# template.net
KiCad netlist of a schematic drawn in Altium Designer
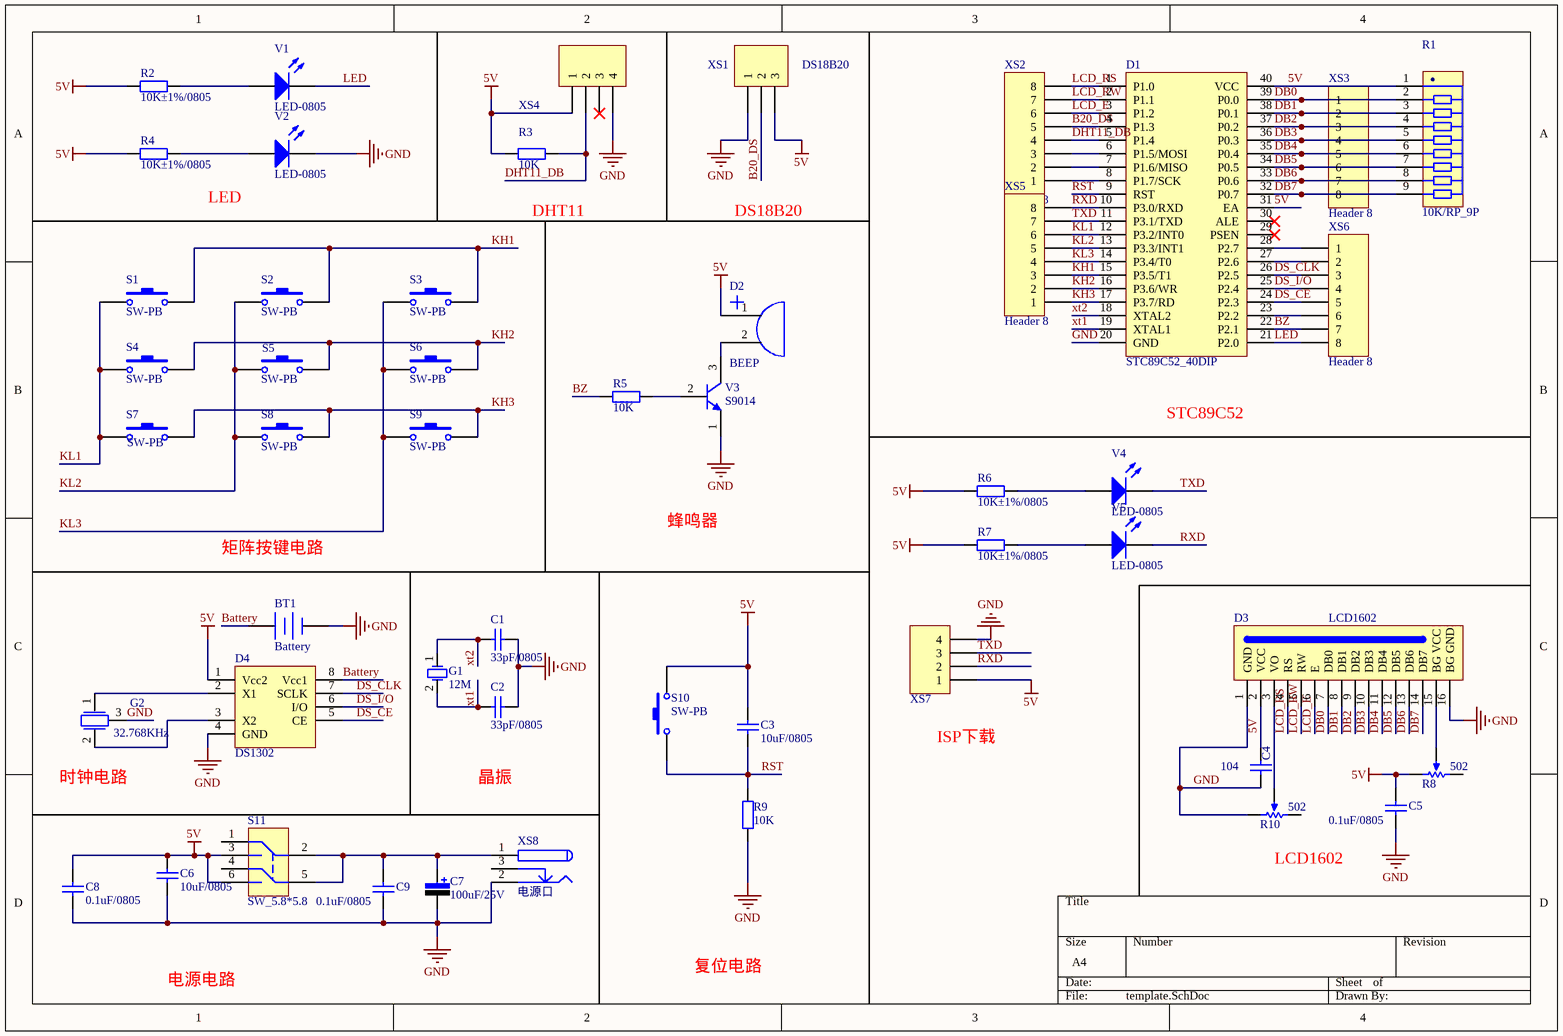
[diagram p0: template.SchDoc]

(export (version "E")
  (design (tool "Eeschema 10.0.6"))
  (components
    (comp (ref "BT1")
      (value "Battery")
      (footprint "CR1220")
      (description "备份电池")
      (fields (field (name "PUBLISHER") "Altium Limited"))
      (libsource (lib "connector") (part "Battery"))
    )
    (comp (ref "C1")
      (value "33pF/0805")
      (footprint "C 0805")
      (description "无极性贴片电容")
      (fields (field (name "PUBLISHER") "Altium Limited"))
      (libsource (lib "C_L_R") (part "Cap1"))
    )
    (comp (ref "C2")
      (value "33pF/0805")
      (footprint "C 0805")
      (description "无极性贴片电容")
      (fields (field (name "PUBLISHER") "Altium Limited"))
      (libsource (lib "C_L_R") (part "Cap1"))
    )
    (comp (ref "C3")
      (value "10uF/0805")
      (footprint "C 0805")
      (description "无极性贴片电容")
      (fields (field (name "PUBLISHER") "Altium Limited"))
      (libsource (lib "C_L_R") (part "Cap1"))
    )
    (comp (ref "C4")
      (value "104")
      (footprint "C 0805")
      (description "无极性贴片电容")
      (fields (field (name "PUBLISHER") "Altium Limited"))
      (libsource (lib "C_L_R") (part "Cap1"))
    )
    (comp (ref "C5")
      (value "0.1uF/0805")
      (footprint "C 0805")
      (description "无极性贴片电容")
      (fields (field (name "PUBLISHER") "Altium Limited"))
      (libsource (lib "C_L_R") (part "Cap1"))
    )
    (comp (ref "C6")
      (value "10uF/0805")
      (footprint "C 0805")
      (description "无极性贴片电容")
      (fields (field (name "PUBLISHER") "Altium Limited"))
      (libsource (lib "C_L_R") (part "Cap1"))
    )
    (comp (ref "C7")
      (value "100uF/25V")
      (footprint "C-RB-D6.3")
      (description "贴片极性电解电容")
      (fields (field (name "PUBLISHER") "Altium Limited"))
      (libsource (lib "C_L_R") (part "Cap Pol2"))
    )
    (comp (ref "C8")
      (value "0.1uF/0805")
      (footprint "C 0805")
      (description "无极性贴片电容")
      (fields (field (name "PUBLISHER") "Altium Limited"))
      (libsource (lib "C_L_R") (part "Cap1"))
    )
    (comp (ref "C9")
      (value "0.1uF/0805")
      (footprint "C 0805")
      (description "无极性贴片电容")
      (fields (field (name "PUBLISHER") "Altium Limited"))
      (libsource (lib "C_L_R") (part "Cap1"))
    )
    (comp (ref "D1")
      (value "STC89C52_40DIP")
      (footprint "STC89C52底座")
      (description "40 DIP")
      (libsource (lib "chip") (part "STC89C52_40DIP"))
    )
    (comp (ref "D2")
      (value "BEEP")
      (footprint "Beep")
      (description "蜂鸣器")
      (libsource (lib "chip") (part "BEEP"))
    )
    (comp (ref "D3")
      (value "LCD1602")
      (footprint "LCD1602接口")
      (description "LCD1602接口，16P")
      (libsource (lib "chip") (part "LCD1602接口"))
    )
    (comp (ref "D4")
      (value "DS1302")
      (footprint "DS1302")
      (description "实时时钟芯片")
      (libsource (lib "chip") (part "DS1302"))
    )
    (comp (ref "G1")
      (value "12M")
      (footprint "XTAL-HC-49S")
      (description "2脚晶振")
      (fields (field (name "PUBLISHER") "Altium Limited"))
      (libsource (lib "chip") (part "XTAL-2P"))
    )
    (comp (ref "G2")
      (value "32.768KHz")
      (footprint "XTAL-TC15")
      (description "3脚晶振")
      (libsource (lib "chip") (part "XTAL-3P"))
    )
    (comp (ref "R1")
      (value "10K/RP_9P")
      (footprint "RP_9P")
      (description "9P排阻")
      (libsource (lib "C_L_R") (part "RP_9P"))
    )
    (comp (ref "R2")
      (value "10K±1%/0805")
      (footprint "R 0805")
      (description "贴片电阻")
      (fields (field (name "PUBLISHER") "Altium Limited"))
      (libsource (lib "C_L_R") (part "Res1"))
    )
    (comp (ref "R3")
      (value "10K")
      (footprint "R 0805")
      (description "贴片电阻")
      (fields (field (name "PUBLISHER") "Altium Limited"))
      (libsource (lib "C_L_R") (part "Res1"))
    )
    (comp (ref "R4")
      (value "10K±1%/0805")
      (footprint "R 0805")
      (description "贴片电阻")
      (fields (field (name "PUBLISHER") "Altium Limited"))
      (libsource (lib "C_L_R") (part "Res1"))
    )
    (comp (ref "R5")
      (value "10K")
      (footprint "R 0805")
      (description "贴片电阻")
      (fields (field (name "PUBLISHER") "Altium Limited"))
      (libsource (lib "C_L_R") (part "Res1"))
    )
    (comp (ref "R6")
      (value "10K±1%/0805")
      (footprint "R 0805")
      (description "贴片电阻")
      (fields (field (name "PUBLISHER") "Altium Limited"))
      (libsource (lib "C_L_R") (part "Res1"))
    )
    (comp (ref "R7")
      (value "10K±1%/0805")
      (footprint "R 0805")
      (description "贴片电阻")
      (fields (field (name "PUBLISHER") "Altium Limited"))
      (libsource (lib "C_L_R") (part "Res1"))
    )
    (comp (ref "R8")
      (value "502")
      (footprint "RP")
      (description "精密可调电阻")
      (fields (field (name "PUBLISHER") "Altium Limited"))
      (libsource (lib "C_L_R") (part "RPot"))
    )
    (comp (ref "R9")
      (value "10K")
      (footprint "R 0805")
      (description "贴片电阻")
      (fields (field (name "PUBLISHER") "Altium Limited"))
      (libsource (lib "") (part "Res1_1"))
    )
    (comp (ref "R10")
      (value "502")
      (footprint "RP")
      (description "精密可调电阻")
      (fields (field (name "PUBLISHER") "Altium Limited"))
      (libsource (lib "C_L_R") (part "RPot"))
    )
    (comp (ref "S1")
      (value "SW-PB")
      (footprint "SW_PB2_A1")
      (description "微动开关")
      (fields (field (name "PUBLISHER") "Altium Limited"))
      (libsource (lib "connector") (part "SW-PB"))
    )
    (comp (ref "S2")
      (value "SW-PB")
      (footprint "SW_PB2_A1")
      (description "微动开关")
      (fields (field (name "PUBLISHER") "Altium Limited"))
      (libsource (lib "connector") (part "SW-PB"))
    )
    (comp (ref "S3")
      (value "SW-PB")
      (footprint "SW_PB2_A1")
      (description "微动开关")
      (fields (field (name "PUBLISHER") "Altium Limited"))
      (libsource (lib "connector") (part "SW-PB"))
    )
    (comp (ref "S4")
      (value "SW-PB")
      (footprint "SW_PB2_A1")
      (description "微动开关")
      (fields (field (name "PUBLISHER") "Altium Limited"))
      (libsource (lib "connector") (part "SW-PB"))
    )
    (comp (ref "S5")
      (value "SW-PB")
      (footprint "SW_PB2_A1")
      (description "微动开关")
      (fields (field (name "PUBLISHER") "Altium Limited"))
      (libsource (lib "connector") (part "SW-PB"))
    )
    (comp (ref "S6")
      (value "SW-PB")
      (footprint "SW_PB2_A1")
      (description "微动开关")
      (fields (field (name "PUBLISHER") "Altium Limited"))
      (libsource (lib "connector") (part "SW-PB"))
    )
    (comp (ref "S7")
      (value "SW-PB")
      (footprint "SW_PB2_A1")
      (description "微动开关")
      (fields (field (name "PUBLISHER") "Altium Limited"))
      (libsource (lib "connector") (part "SW-PB"))
    )
    (comp (ref "S8")
      (value "SW-PB")
      (footprint "SW_PB2_A1")
      (description "微动开关")
      (fields (field (name "PUBLISHER") "Altium Limited"))
      (libsource (lib "connector") (part "SW-PB"))
    )
    (comp (ref "S9")
      (value "SW-PB")
      (footprint "SW_PB2_A1")
      (description "微动开关")
      (fields (field (name "PUBLISHER") "Altium Limited"))
      (libsource (lib "connector") (part "SW-PB"))
    )
    (comp (ref "S10")
      (value "SW-PB")
      (footprint "SW_PB2_A1")
      (description "微动开关")
      (fields (field (name "PUBLISHER") "Altium Limited"))
      (libsource (lib "connector") (part "SW-PB"))
    )
    (comp (ref "S11")
      (value "SW_5.8*5.8")
      (footprint "SW-5.8")
      (description "6脚自锁开关")
      (libsource (lib "connector") (part "SW-6脚自锁开关"))
    )
    (comp (ref "V1")
      (value "LED-0805")
      (footprint "LED-0805")
      (description "发光二极管")
      (fields (field (name "PUBLISHER") "Altium Limited"))
      (libsource (lib "C_L_R") (part "LED0"))
    )
    (comp (ref "V2")
      (value "LED-0805")
      (footprint "LED-0805")
      (description "发光二极管")
      (fields (field (name "PUBLISHER") "Altium Limited"))
      (libsource (lib "C_L_R") (part "LED0"))
    )
    (comp (ref "V3")
      (value "S9014")
      (footprint "SS9014")
      (description "NPN三极管")
      (fields (field (name "PUBLISHER") "Altium Limited"))
      (libsource (lib "chip") (part "S9014"))
    )
    (comp (ref "V4")
      (value "LED-0805")
      (footprint "LED-0805")
      (description "发光二极管")
      (fields (field (name "PUBLISHER") "Altium Limited"))
      (libsource (lib "C_L_R") (part "LED0"))
    )
    (comp (ref "V5")
      (value "LED-0805")
      (footprint "LED-0805")
      (description "发光二极管")
      (fields (field (name "PUBLISHER") "Altium Limited"))
      (libsource (lib "C_L_R") (part "LED0"))
    )
    (comp (ref "XS1")
      (value "DS18B20")
      (footprint "HDR3X1_A")
      (description "接插件")
      (fields (field (name "PUBLISHER") "Altium Limited"))
      (libsource (lib "connector") (part "Header 3"))
    )
    (comp (ref "XS2")
      (value "Header 8")
      (footprint "HDR8X1_A")
      (description "Header, 8-Pin")
      (fields (field (name "PUBLISHER") "Altium Limited"))
      (libsource (lib "connector") (part "Header 8"))
    )
    (comp (ref "XS3")
      (value "Header 8")
      (footprint "HDR8X1_A")
      (description "Header, 8-Pin")
      (fields (field (name "PUBLISHER") "Altium Limited"))
      (libsource (lib "") (part "Header 8_1"))
    )
    (comp (ref "XS4")
      (value "Header 4")
      (footprint "HDR4X1_A")
      (description "接插件")
      (fields (field (name "PUBLISHER") "Altium Limited"))
      (libsource (lib "") (part "Header 4_1"))
    )
    (comp (ref "XS5")
      (value "Header 8")
      (footprint "HDR8X1_A")
      (description "Header, 8-Pin")
      (fields (field (name "PUBLISHER") "Altium Limited"))
      (libsource (lib "connector") (part "Header 8"))
    )
    (comp (ref "XS6")
      (value "Header 8")
      (footprint "HDR8X1_A")
      (description "Header, 8-Pin")
      (fields (field (name "PUBLISHER") "Altium Limited"))
      (libsource (lib "") (part "Header 8_1"))
    )
    (comp (ref "XS7")
      (value "Header 4")
      (footprint "HDR4X1_A")
      (description "接插件")
      (fields (field (name "PUBLISHER") "Altium Limited"))
      (libsource (lib "connector") (part "Header 4"))
    )
    (comp (ref "XS8")
      (value "电源口")
      (footprint "DC-005")
      (description "直流电源端子")
      (fields (field (name "PUBLISHER") "Altium Limited"))
      (libsource (lib "connector") (part "DC connector"))
    )
  )
  (nets
    (net (code "1") (name "/B20_DS") (class "Default")
      (node (ref "D1") (pin "4") (pinfunction "P1.3_4") (pintype "passive"))
      (node (ref "XS1") (pin "2") (pinfunction "2_2") (pintype "passive"))
      (node (ref "XS2") (pin "5") (pinfunction "5_5") (pintype "passive"))
    )
    (net (code "2") (name "/BZ") (class "Default")
      (node (ref "D1") (pin "22") (pinfunction "P2.1_22") (pintype "passive"))
      (node (ref "R5") (pin "1") (pinfunction "1_1") (pintype "passive"))
      (node (ref "XS6") (pin "7") (pinfunction "7_7") (pintype "passive"))
    )
    (net (code "3") (name "/Battery") (class "Default")
      (node (ref "BT1") (pin "1") (pinfunction "+_1") (pintype "passive"))
      (node (ref "D4") (pin "8") (pinfunction "Vcc1_8") (pintype "passive"))
    )
    (net (code "4") (name "/DB0") (class "Default")
      (node (ref "D1") (pin "39") (pinfunction "P0.0_39") (pintype "passive"))
      (node (ref "D3") (pin "7") (pinfunction "DB0_7") (pintype "passive"))
      (node (ref "R1") (pin "2") (pinfunction "2_2") (pintype "power_in"))
      (node (ref "XS3") (pin "1") (pinfunction "1_1") (pintype "passive"))
    )
    (net (code "5") (name "/DB1") (class "Default")
      (node (ref "D1") (pin "38") (pinfunction "P0.1_38") (pintype "passive"))
      (node (ref "D3") (pin "8") (pinfunction "DB1_8") (pintype "passive"))
      (node (ref "R1") (pin "3") (pinfunction "3_3") (pintype "power_in"))
      (node (ref "XS3") (pin "2") (pinfunction "2_2") (pintype "passive"))
    )
    (net (code "6") (name "/DB2") (class "Default")
      (node (ref "D1") (pin "37") (pinfunction "P0.2_37") (pintype "passive"))
      (node (ref "D3") (pin "9") (pinfunction "DB2_9") (pintype "passive"))
      (node (ref "R1") (pin "4") (pinfunction "4_4") (pintype "power_in"))
      (node (ref "XS3") (pin "3") (pinfunction "3_3") (pintype "passive"))
    )
    (net (code "7") (name "/DB3") (class "Default")
      (node (ref "D1") (pin "36") (pinfunction "P0.3_36") (pintype "passive"))
      (node (ref "D3") (pin "10") (pinfunction "DB3_10") (pintype "passive"))
      (node (ref "R1") (pin "5") (pinfunction "5_5") (pintype "power_in"))
      (node (ref "XS3") (pin "4") (pinfunction "4_4") (pintype "passive"))
    )
    (net (code "8") (name "/DB4") (class "Default")
      (node (ref "D1") (pin "35") (pinfunction "P0.4_35") (pintype "passive"))
      (node (ref "D3") (pin "11") (pinfunction "DB4_11") (pintype "passive"))
      (node (ref "R1") (pin "6") (pinfunction "6_6") (pintype "power_in"))
      (node (ref "XS3") (pin "5") (pinfunction "5_5") (pintype "passive"))
    )
    (net (code "9") (name "/DB5") (class "Default")
      (node (ref "D1") (pin "34") (pinfunction "P0.5_34") (pintype "passive"))
      (node (ref "D3") (pin "12") (pinfunction "DB5_12") (pintype "passive"))
      (node (ref "R1") (pin "7") (pinfunction "7_7") (pintype "power_in"))
      (node (ref "XS3") (pin "6") (pinfunction "6_6") (pintype "passive"))
    )
    (net (code "10") (name "/DB6") (class "Default")
      (node (ref "D1") (pin "33") (pinfunction "P0.6_33") (pintype "passive"))
      (node (ref "D3") (pin "13") (pinfunction "DB6_13") (pintype "passive"))
      (node (ref "R1") (pin "8") (pinfunction "8_8") (pintype "power_in"))
      (node (ref "XS3") (pin "7") (pinfunction "7_7") (pintype "passive"))
    )
    (net (code "11") (name "/DB7") (class "Default")
      (node (ref "D1") (pin "32") (pinfunction "P0.7_32") (pintype "passive"))
      (node (ref "D3") (pin "14") (pinfunction "DB7_14") (pintype "passive"))
      (node (ref "R1") (pin "9") (pinfunction "9_9") (pintype "power_in"))
      (node (ref "XS3") (pin "8") (pinfunction "8_8") (pintype "passive"))
    )
    (net (code "12") (name "/DHT11_DB") (class "Default")
      (node (ref "D1") (pin "5") (pinfunction "P1.4_5") (pintype "passive"))
      (node (ref "R3") (pin "2") (pinfunction "2_2") (pintype "passive"))
      (node (ref "XS2") (pin "4") (pinfunction "4_4") (pintype "passive"))
      (node (ref "XS4") (pin "2") (pinfunction "2_2") (pintype "passive"))
    )
    (net (code "13") (name "/DS_CE") (class "Default")
      (node (ref "D1") (pin "24") (pinfunction "P2.3_24") (pintype "passive"))
      (node (ref "D4") (pin "5") (pinfunction "CE_5") (pintype "passive"))
      (node (ref "XS6") (pin "5") (pinfunction "5_5") (pintype "passive"))
    )
    (net (code "14") (name "/DS_CLK") (class "Default")
      (node (ref "D1") (pin "26") (pinfunction "P2.5_26") (pintype "passive"))
      (node (ref "D4") (pin "7") (pinfunction "SCLK_7") (pintype "passive"))
      (node (ref "XS6") (pin "3") (pinfunction "3_3") (pintype "passive"))
    )
    (net (code "15") (name "/DS_I{slash}O") (class "Default")
      (node (ref "D1") (pin "25") (pinfunction "P2.4_25") (pintype "passive"))
      (node (ref "D4") (pin "6") (pinfunction "I/O_6") (pintype "passive"))
      (node (ref "XS6") (pin "4") (pinfunction "4_4") (pintype "passive"))
    )
    (net (code "16") (name "/KH1") (class "Default")
      (node (ref "D1") (pin "15") (pinfunction "P3.5/T1_15") (pintype "passive"))
      (node (ref "S1") (pin "2") (pinfunction "2_2") (pintype "passive"))
      (node (ref "S2") (pin "2") (pinfunction "2_2") (pintype "passive"))
      (node (ref "S3") (pin "2") (pinfunction "2_2") (pintype "passive"))
      (node (ref "XS5") (pin "3") (pinfunction "3_3") (pintype "passive"))
    )
    (net (code "17") (name "/KH2") (class "Default")
      (node (ref "D1") (pin "16") (pinfunction "P3.6/WR_16") (pintype "passive"))
      (node (ref "S4") (pin "2") (pinfunction "2_2") (pintype "passive"))
      (node (ref "S5") (pin "2") (pinfunction "2_2") (pintype "passive"))
      (node (ref "S6") (pin "2") (pinfunction "2_2") (pintype "passive"))
      (node (ref "XS5") (pin "2") (pinfunction "2_2") (pintype "passive"))
    )
    (net (code "18") (name "/KH3") (class "Default")
      (node (ref "D1") (pin "17") (pinfunction "P3.7/RD_17") (pintype "passive"))
      (node (ref "S7") (pin "2") (pinfunction "2_2") (pintype "passive"))
      (node (ref "S8") (pin "2") (pinfunction "2_2") (pintype "passive"))
      (node (ref "S9") (pin "2") (pinfunction "2_2") (pintype "passive"))
      (node (ref "XS5") (pin "1") (pinfunction "1_1") (pintype "passive"))
    )
    (net (code "19") (name "/KL1") (class "Default")
      (node (ref "D1") (pin "12") (pinfunction "P3.2/INT0_12") (pintype "passive"))
      (node (ref "S1") (pin "1") (pinfunction "1_1") (pintype "passive"))
      (node (ref "S4") (pin "1") (pinfunction "1_1") (pintype "passive"))
      (node (ref "S7") (pin "1") (pinfunction "1_1") (pintype "passive"))
      (node (ref "XS5") (pin "6") (pinfunction "6_6") (pintype "passive"))
    )
    (net (code "20") (name "/KL2") (class "Default")
      (node (ref "D1") (pin "13") (pinfunction "P3.3/INT1_13") (pintype "passive"))
      (node (ref "S2") (pin "1") (pinfunction "1_1") (pintype "passive"))
      (node (ref "S5") (pin "1") (pinfunction "1_1") (pintype "passive"))
      (node (ref "S8") (pin "1") (pinfunction "1_1") (pintype "passive"))
      (node (ref "XS5") (pin "5") (pinfunction "5_5") (pintype "passive"))
    )
    (net (code "21") (name "/KL3") (class "Default")
      (node (ref "D1") (pin "14") (pinfunction "P3.4/T0_14") (pintype "passive"))
      (node (ref "S3") (pin "1") (pinfunction "1_1") (pintype "passive"))
      (node (ref "S6") (pin "1") (pinfunction "1_1") (pintype "passive"))
      (node (ref "S9") (pin "1") (pinfunction "1_1") (pintype "passive"))
      (node (ref "XS5") (pin "4") (pinfunction "4_4") (pintype "passive"))
    )
    (net (code "22") (name "/LCD_E") (class "Default")
      (node (ref "D1") (pin "3") (pinfunction "P1.2_3") (pintype "passive"))
      (node (ref "D3") (pin "6") (pinfunction "E_6") (pintype "passive"))
      (node (ref "XS2") (pin "6") (pinfunction "6_6") (pintype "passive"))
    )
    (net (code "23") (name "/LCD_RS") (class "Default")
      (node (ref "D1") (pin "1") (pinfunction "P1.0_1") (pintype "passive"))
      (node (ref "D3") (pin "4") (pinfunction "RS_4") (pintype "passive"))
      (node (ref "XS2") (pin "8") (pinfunction "8_8") (pintype "passive"))
    )
    (net (code "24") (name "/LCD_RW") (class "Default")
      (node (ref "D1") (pin "2") (pinfunction "P1.1_2") (pintype "passive"))
      (node (ref "D3") (pin "5") (pinfunction "RW_5") (pintype "passive"))
      (node (ref "XS2") (pin "7") (pinfunction "7_7") (pintype "passive"))
    )
    (net (code "25") (name "/LED") (class "Default")
      (node (ref "D1") (pin "21") (pinfunction "P2.0_21") (pintype "passive"))
      (node (ref "V1") (pin "2") (pinfunction "K_2") (pintype "passive"))
      (node (ref "XS6") (pin "8") (pinfunction "8_8") (pintype "passive"))
    )
    (net (code "26") (name "/RST") (class "Default")
      (node (ref "C3") (pin "1") (pinfunction "1_1") (pintype "passive"))
      (node (ref "D1") (pin "9") (pinfunction "RST_9") (pintype "passive"))
      (node (ref "R9") (pin "2") (pinfunction "2_2") (pintype "passive"))
      (node (ref "S10") (pin "1") (pinfunction "1_1") (pintype "passive"))
    )
    (net (code "27") (name "/RXD") (class "Default")
      (node (ref "D1") (pin "10") (pinfunction "P3.0/RXD_10") (pintype "passive"))
      (node (ref "V5") (pin "2") (pinfunction "K_2") (pintype "passive"))
      (node (ref "XS5") (pin "8") (pinfunction "8_8") (pintype "passive"))
      (node (ref "XS7") (pin "2") (pinfunction "2_2") (pintype "passive"))
    )
    (net (code "28") (name "/TXD") (class "Default")
      (node (ref "D1") (pin "11") (pinfunction "P3.1/TXD_11") (pintype "passive"))
      (node (ref "V4") (pin "2") (pinfunction "K_2") (pintype "passive"))
      (node (ref "XS5") (pin "7") (pinfunction "7_7") (pintype "passive"))
      (node (ref "XS7") (pin "3") (pinfunction "3_3") (pintype "passive"))
    )
    (net (code "29") (name "/xt1") (class "Default")
      (node (ref "C2") (pin "2") (pinfunction "2_2") (pintype "passive"))
      (node (ref "D1") (pin "19") (pinfunction "XTAL1_19") (pintype "passive"))
      (node (ref "G1") (pin "2") (pinfunction "2_2") (pintype "passive"))
    )
    (net (code "30") (name "/xt2") (class "Default")
      (node (ref "C1") (pin "1") (pinfunction "1_1") (pintype "passive"))
      (node (ref "D1") (pin "18") (pinfunction "XTAL2_18") (pintype "passive"))
      (node (ref "G1") (pin "1") (pinfunction "1_1") (pintype "passive"))
    )
    (net (code "31") (name "5V") (class "Default")
      (node (ref "C3") (pin "2") (pinfunction "2_2") (pintype "passive"))
      (node (ref "C4") (pin "2") (pinfunction "2_2") (pintype "passive"))
      (node (ref "C5") (pin "2") (pinfunction "2_2") (pintype "passive"))
      (node (ref "C6") (pin "2") (pinfunction "2_2") (pintype "passive"))
      (node (ref "C8") (pin "2") (pinfunction "2_2") (pintype "passive"))
      (node (ref "D1") (pin "31") (pinfunction "EA_31") (pintype "passive"))
      (node (ref "D1") (pin "40") (pinfunction "VCC_40") (pintype "passive"))
      (node (ref "D2") (pin "1") (pinfunction "0_1") (pintype "passive"))
      (node (ref "D3") (pin "2") (pinfunction "VCC_2") (pintype "passive"))
      (node (ref "D4") (pin "1") (pinfunction "Vcc2_1") (pintype "passive"))
      (node (ref "R1") (pin "1") (pinfunction "1_1") (pintype "power_in"))
      (node (ref "R2") (pin "1") (pinfunction "1_1") (pintype "passive"))
      (node (ref "R3") (pin "1") (pinfunction "1_1") (pintype "passive"))
      (node (ref "R4") (pin "1") (pinfunction "1_1") (pintype "passive"))
      (node (ref "R6") (pin "1") (pinfunction "1_1") (pintype "passive"))
      (node (ref "R7") (pin "1") (pinfunction "1_1") (pintype "passive"))
      (node (ref "R8") (pin "3") (pinfunction "BOT_3") (pintype "passive"))
      (node (ref "S10") (pin "2") (pinfunction "2_2") (pintype "passive"))
      (node (ref "S11") (pin "3") (pinfunction "3_3") (pintype "passive"))
      (node (ref "S11") (pin "6") (pinfunction "6_6") (pintype "passive"))
      (node (ref "XS1") (pin "3") (pinfunction "3_3") (pintype "passive"))
      (node (ref "XS4") (pin "1") (pinfunction "1_1") (pintype "passive"))
      (node (ref "XS7") (pin "1") (pinfunction "1_1") (pintype "passive"))
    )
    (net (code "32") (name "GND") (class "Default")
      (node (ref "BT1") (pin "2") (pinfunction "-_2") (pintype "passive"))
      (node (ref "C1") (pin "2") (pinfunction "2_2") (pintype "passive"))
      (node (ref "C2") (pin "1") (pinfunction "1_1") (pintype "passive"))
      (node (ref "C4") (pin "1") (pinfunction "1_1") (pintype "passive"))
      (node (ref "C5") (pin "1") (pinfunction "1_1") (pintype "passive"))
      (node (ref "C6") (pin "1") (pinfunction "1_1") (pintype "passive"))
      (node (ref "C7") (pin "2") (pinfunction "2_2") (pintype "passive"))
      (node (ref "C8") (pin "1") (pinfunction "1_1") (pintype "passive"))
      (node (ref "C9") (pin "1") (pinfunction "1_1") (pintype "passive"))
      (node (ref "D1") (pin "20") (pinfunction "GND_20") (pintype "passive"))
      (node (ref "D3") (pin "1") (pinfunction "GND_1") (pintype "passive"))
      (node (ref "D3") (pin "16") (pinfunction "BG_GND_16") (pintype "passive"))
      (node (ref "D4") (pin "4") (pinfunction "GND_4") (pintype "passive"))
      (node (ref "G2") (pin "3") (pinfunction "3_3") (pintype "passive"))
      (node (ref "R10") (pin "3") (pinfunction "BOT_3") (pintype "passive"))
      (node (ref "R9") (pin "1") (pinfunction "1_1") (pintype "passive"))
      (node (ref "V2") (pin "2") (pinfunction "K_2") (pintype "passive"))
      (node (ref "V3") (pin "1") (pinfunction "E_1") (pintype "passive"))
      (node (ref "XS1") (pin "1") (pinfunction "1_1") (pintype "passive"))
      (node (ref "XS4") (pin "4") (pinfunction "4_4") (pintype "passive"))
      (node (ref "XS7") (pin "4") (pinfunction "4_4") (pintype "passive"))
      (node (ref "XS8") (pin "2") (pinfunction "2_2") (pintype "power_in"))
    )
    (net (code "33") (name "Net-(C7-Pad1)") (class "Default")
      (node (ref "C7") (pin "1") (pinfunction "1_1") (pintype "passive"))
      (node (ref "C9") (pin "2") (pinfunction "2_2") (pintype "passive"))
      (node (ref "S11") (pin "2") (pinfunction "2_2") (pintype "passive"))
      (node (ref "S11") (pin "5") (pinfunction "5_5") (pintype "passive"))
      (node (ref "XS8") (pin "1") (pinfunction "1_1") (pintype "power_in"))
    )
    (net (code "34") (name "Net-(D1-P1.5{slash}MOSI)") (class "Default")
      (node (ref "D1") (pin "6") (pinfunction "P1.5/MOSI_6") (pintype "passive"))
      (node (ref "XS2") (pin "3") (pinfunction "3_3") (pintype "passive"))
    )
    (net (code "35") (name "Net-(D1-P1.6{slash}MISO)") (class "Default")
      (node (ref "D1") (pin "7") (pinfunction "P1.6/MISO_7") (pintype "passive"))
      (node (ref "XS2") (pin "2") (pinfunction "2_2") (pintype "passive"))
    )
    (net (code "36") (name "Net-(D1-P1.7{slash}SCK)") (class "Default")
      (node (ref "D1") (pin "8") (pinfunction "P1.7/SCK_8") (pintype "passive"))
      (node (ref "XS2") (pin "1") (pinfunction "1_1") (pintype "passive"))
    )
    (net (code "37") (name "Net-(D1-P2.2)") (class "Default")
      (node (ref "D1") (pin "23") (pinfunction "P2.2_23") (pintype "passive"))
      (node (ref "XS6") (pin "6") (pinfunction "6_6") (pintype "passive"))
    )
    (net (code "38") (name "Net-(D1-P2.6)") (class "Default")
      (node (ref "D1") (pin "27") (pinfunction "P2.6_27") (pintype "passive"))
      (node (ref "XS6") (pin "2") (pinfunction "2_2") (pintype "passive"))
    )
    (net (code "39") (name "Net-(D1-P2.7)") (class "Default")
      (node (ref "D1") (pin "28") (pinfunction "P2.7_28") (pintype "passive"))
      (node (ref "XS6") (pin "1") (pinfunction "1_1") (pintype "passive"))
    )
    (net (code "40") (name "Net-(D2-1)") (class "Default")
      (node (ref "D2") (pin "2") (pinfunction "1_2") (pintype "passive"))
      (node (ref "V3") (pin "3") (pinfunction "C_3") (pintype "passive"))
    )
    (net (code "41") (name "Net-(D3-BG_VCC)") (class "Default")
      (node (ref "D3") (pin "15") (pinfunction "BG_VCC_15") (pintype "passive"))
      (node (ref "R8") (pin "2") (pinfunction "TAP_2") (pintype "passive"))
    )
    (net (code "42") (name "Net-(D3-VO)") (class "Default")
      (node (ref "D3") (pin "3") (pinfunction "VO_3") (pintype "passive"))
      (node (ref "R10") (pin "2") (pinfunction "TAP_2") (pintype "passive"))
    )
    (net (code "43") (name "Net-(D4-X1)") (class "Default")
      (node (ref "D4") (pin "2") (pinfunction "X1_2") (pintype "passive"))
      (node (ref "G2") (pin "1") (pinfunction "1_1") (pintype "passive"))
    )
    (net (code "44") (name "Net-(D4-X2)") (class "Default")
      (node (ref "D4") (pin "3") (pinfunction "X2_3") (pintype "passive"))
      (node (ref "G2") (pin "2") (pinfunction "2_2") (pintype "passive"))
    )
    (net (code "45") (name "Net-(V1-A)") (class "Default")
      (node (ref "R2") (pin "2") (pinfunction "2_2") (pintype "passive"))
      (node (ref "V1") (pin "1") (pinfunction "A_1") (pintype "passive"))
    )
    (net (code "46") (name "Net-(V2-A)") (class "Default")
      (node (ref "R4") (pin "2") (pinfunction "2_2") (pintype "passive"))
      (node (ref "V2") (pin "1") (pinfunction "A_1") (pintype "passive"))
    )
    (net (code "47") (name "Net-(V3-B)") (class "Default")
      (node (ref "R5") (pin "2") (pinfunction "2_2") (pintype "passive"))
      (node (ref "V3") (pin "2") (pinfunction "B_2") (pintype "passive"))
    )
    (net (code "48") (name "Net-(V4-A)") (class "Default")
      (node (ref "R6") (pin "2") (pinfunction "2_2") (pintype "passive"))
      (node (ref "V4") (pin "1") (pinfunction "A_1") (pintype "passive"))
    )
    (net (code "49") (name "Net-(V5-A)") (class "Default")
      (node (ref "R7") (pin "2") (pinfunction "2_2") (pintype "passive"))
      (node (ref "V5") (pin "1") (pinfunction "A_1") (pintype "passive"))
    )
    (net (code "50") (name "unconnected-(D1-ALE-Pad30)") (class "Default")
      (node (ref "D1") (pin "30") (pinfunction "ALE_30") (pintype "passive+no_connect"))
    )
    (net (code "51") (name "unconnected-(D1-PSEN-Pad29)") (class "Default")
      (node (ref "D1") (pin "29") (pinfunction "PSEN_29") (pintype "passive+no_connect"))
    )
    (net (code "52") (name "unconnected-(R8-TOP-Pad1)") (class "Default")
      (node (ref "R8") (pin "1") (pinfunction "TOP_1") (pintype "passive"))
    )
    (net (code "53") (name "unconnected-(R10-TOP-Pad1)") (class "Default")
      (node (ref "R10") (pin "1") (pinfunction "TOP_1") (pintype "passive"))
    )
    (net (code "54") (name "unconnected-(S11-Pad1)") (class "Default")
      (node (ref "S11") (pin "1") (pinfunction "1_1") (pintype "passive"))
    )
    (net (code "55") (name "unconnected-(S11-Pad4)") (class "Default")
      (node (ref "S11") (pin "4") (pinfunction "4_4") (pintype "passive"))
    )
    (net (code "56") (name "unconnected-(XS4-Pad3)") (class "Default")
      (node (ref "XS4") (pin "3") (pinfunction "3_3") (pintype "passive+no_connect"))
    )
    (net (code "57") (name "unconnected-(XS8-Pad3)") (class "Default")
      (node (ref "XS8") (pin "3") (pinfunction "3_3") (pintype "power_in"))
    )
  )
)
